# air-sensors.net
KiCad netlist of a schematic drawn in EAGLE
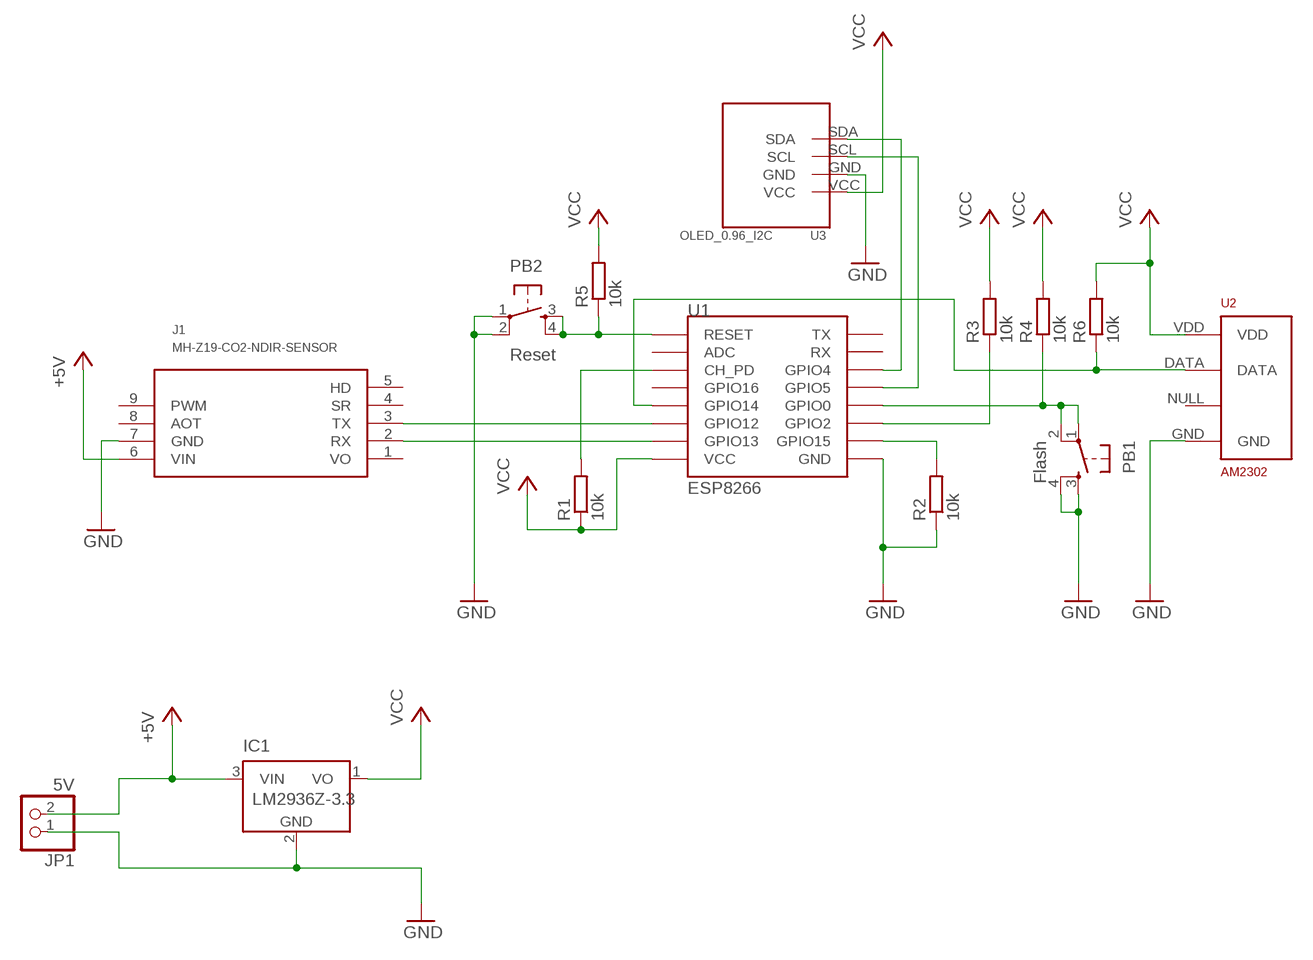
[diagram p0: schematic, sheet 1]

(export (version "E")
  (design (tool "Eeschema 10.0.6"))
  (components
    (comp (ref "IC1")
      (value "LM2936Z-3.3")
      (footprint "eagle-import:TO92")
      (fields (field (name "MF") "NATIONAL SEMICONDUCTOR") (field (name "MPN") "LM2936Z-3.3/NOPB"))
      (libsource (lib "eagle-import") (part "LM2936?Z-3.3"))
    )
    (comp (ref "J1")
      (value "MH-Z19-CO2-NDIR-SENSOR")
      (footprint "eagle-import:MH-Z19")
      (libsource (lib "eagle-import") (part "MH-Z19-CO2-NDIR-SENSOR"))
    )
    (comp (ref "JP1")
      (value "5V")
      (footprint "eagle-import:1X02")
      (libsource (lib "eagle-import") (part "PINHD-1X2"))
    )
    (comp (ref "PB1")
      (value "Flash")
      (footprint "eagle-import:TACTILE-PTH")
      (libsource (lib "eagle-import") (part "TAC_SWITCHPTH"))
    )
    (comp (ref "PB2")
      (value "Reset")
      (footprint "eagle-import:TACTILE-PTH")
      (libsource (lib "eagle-import") (part "TAC_SWITCHPTH"))
    )
    (comp (ref "R1")
      (value "10k")
      (footprint "eagle-import:0204_7")
      (libsource (lib "eagle-import") (part "R-EU_0204/7"))
    )
    (comp (ref "R2")
      (value "10k")
      (footprint "eagle-import:0204_7")
      (libsource (lib "eagle-import") (part "R-EU_0204/7"))
    )
    (comp (ref "R3")
      (value "10k")
      (footprint "eagle-import:0204_7")
      (libsource (lib "eagle-import") (part "R-EU_0204/7"))
    )
    (comp (ref "R4")
      (value "10k")
      (footprint "eagle-import:0204_7")
      (libsource (lib "eagle-import") (part "R-EU_0204/7"))
    )
    (comp (ref "R5")
      (value "10k")
      (footprint "eagle-import:0204_7")
      (libsource (lib "eagle-import") (part "R-EU_0204/7"))
    )
    (comp (ref "R6")
      (value "10k")
      (footprint "eagle-import:0204_7")
      (libsource (lib "eagle-import") (part "R-EU_0204/7"))
    )
    (comp (ref "U1")
      (value "ESP8266")
      (footprint "eagle-import:ESP12")
      (libsource (lib "eagle-import") (part "ESP12"))
    )
    (comp (ref "U2")
      (value "AM2302")
      (footprint "eagle-import:RHT03_DHT-22")
      (libsource (lib "eagle-import") (part "RHT03_DHT-22_AM2302"))
    )
    (comp (ref "U3")
      (value "OLED_0.96_I2C")
      (footprint "eagle-import:OLED_0.96_I2C")
      (libsource (lib "eagle-import") (part "OLED_0.96_I2C"))
    )
  )
  (nets
    (net (code "1") (name "+5V") (class "Default")
      (node (ref "IC1") (pin "3") (pinfunction "VIN_3") (pintype "input"))
      (node (ref "J1") (pin "6") (pinfunction "VIN_6") (pintype "power_in"))
      (node (ref "JP1") (pin "2") (pinfunction "2_2") (pintype "passive"))
    )
    (net (code "2") (name "/VO") (class "Default")
      (node (ref "J1") (pin "1") (pinfunction "VO_1") (pintype "power_in"))
    )
    (net (code "3") (name "GND") (class "Default")
      (node (ref "IC1") (pin "2") (pinfunction "GND_2") (pintype "passive"))
      (node (ref "J1") (pin "7") (pinfunction "GND_7") (pintype "power_in"))
      (node (ref "JP1") (pin "1") (pinfunction "1_1") (pintype "passive"))
      (node (ref "PB1") (pin "3") (pinfunction "3_3") (pintype "passive"))
      (node (ref "PB1") (pin "4") (pinfunction "4_4") (pintype "passive"))
      (node (ref "PB2") (pin "1") (pinfunction "1_1") (pintype "passive"))
      (node (ref "PB2") (pin "2") (pinfunction "2_2") (pintype "passive"))
      (node (ref "R2") (pin "1") (pinfunction "1_1") (pintype "passive"))
      (node (ref "U1") (pin "GND") (pinfunction "GND_GND") (pintype "bidirectional"))
      (node (ref "U2") (pin "GND") (pinfunction "GND_GND") (pintype "power_in"))
      (node (ref "U3") (pin "GND") (pinfunction "GND_GND") (pintype "bidirectional"))
    )
    (net (code "4") (name "Net-(J1-RX)") (class "Default")
      (node (ref "J1") (pin "2") (pinfunction "RX_2") (pintype "input"))
      (node (ref "U1") (pin "GPIO13") (pinfunction "GPIO13_GPIO13") (pintype "bidirectional"))
    )
    (net (code "5") (name "Net-(J1-TX)") (class "Default")
      (node (ref "J1") (pin "3") (pinfunction "TX_3") (pintype "output"))
      (node (ref "U1") (pin "GPIO12") (pinfunction "GPIO12_GPIO12") (pintype "bidirectional"))
    )
    (net (code "6") (name "Net-(PB1-Pad1)") (class "Default")
      (node (ref "PB1") (pin "1") (pinfunction "1_1") (pintype "passive"))
      (node (ref "PB1") (pin "2") (pinfunction "2_2") (pintype "passive"))
      (node (ref "R4") (pin "1") (pinfunction "1_1") (pintype "passive"))
      (node (ref "U1") (pin "GPIO0") (pinfunction "GPIO0_GPIO0") (pintype "bidirectional"))
    )
    (net (code "7") (name "Net-(PB2-Pad3)") (class "Default")
      (node (ref "PB2") (pin "3") (pinfunction "3_3") (pintype "passive"))
      (node (ref "PB2") (pin "4") (pinfunction "4_4") (pintype "passive"))
      (node (ref "R5") (pin "1") (pinfunction "1_1") (pintype "passive"))
      (node (ref "U1") (pin "RESET") (pinfunction "RESET_RESET") (pintype "bidirectional"))
    )
    (net (code "8") (name "Net-(R1-Pad2)") (class "Default")
      (node (ref "R1") (pin "2") (pinfunction "2_2") (pintype "passive"))
      (node (ref "U1") (pin "CH_PD") (pinfunction "CH_PD_CH_PD") (pintype "bidirectional"))
    )
    (net (code "9") (name "Net-(R2-Pad2)") (class "Default")
      (node (ref "R2") (pin "2") (pinfunction "2_2") (pintype "passive"))
      (node (ref "U1") (pin "GPIO15") (pinfunction "GPIO15_GPIO15") (pintype "bidirectional"))
    )
    (net (code "10") (name "Net-(R3-Pad1)") (class "Default")
      (node (ref "R3") (pin "1") (pinfunction "1_1") (pintype "passive"))
      (node (ref "U1") (pin "GPIO2") (pinfunction "GPIO2_GPIO2") (pintype "bidirectional"))
    )
    (net (code "11") (name "Net-(R6-Pad1)") (class "Default")
      (node (ref "R6") (pin "1") (pinfunction "1_1") (pintype "passive"))
      (node (ref "U1") (pin "GPIO14") (pinfunction "GPIO14_GPIO14") (pintype "bidirectional"))
      (node (ref "U2") (pin "DATA") (pinfunction "DATA_DATA") (pintype "bidirectional"))
    )
    (net (code "12") (name "Net-(U1-PadGPIO4)") (class "Default")
      (node (ref "U1") (pin "GPIO4") (pinfunction "GPIO4_GPIO4") (pintype "bidirectional"))
      (node (ref "U3") (pin "SDA") (pinfunction "SDA_SDA") (pintype "bidirectional"))
    )
    (net (code "13") (name "Net-(U1-PadGPIO5)") (class "Default")
      (node (ref "U1") (pin "GPIO5") (pinfunction "GPIO5_GPIO5") (pintype "bidirectional"))
      (node (ref "U3") (pin "SCL") (pinfunction "SCL_SCL") (pintype "bidirectional"))
    )
    (net (code "14") (name "VCC") (class "Default")
      (node (ref "IC1") (pin "1") (pinfunction "VO_1") (pintype "passive"))
      (node (ref "R1") (pin "1") (pinfunction "1_1") (pintype "passive"))
      (node (ref "R3") (pin "2") (pinfunction "2_2") (pintype "passive"))
      (node (ref "R4") (pin "2") (pinfunction "2_2") (pintype "passive"))
      (node (ref "R5") (pin "2") (pinfunction "2_2") (pintype "passive"))
      (node (ref "R6") (pin "2") (pinfunction "2_2") (pintype "passive"))
      (node (ref "U1") (pin "VCC") (pinfunction "VCC_VCC") (pintype "bidirectional"))
      (node (ref "U2") (pin "VDD") (pinfunction "VDD_VDD") (pintype "power_in"))
      (node (ref "U3") (pin "VCC") (pinfunction "VCC_VCC") (pintype "bidirectional"))
    )
    (net (code "15") (name "unconnected-(J1-AOT-Pad8)") (class "Default")
      (node (ref "J1") (pin "8") (pinfunction "AOT_8") (pintype "no_connect"))
    )
    (net (code "16") (name "unconnected-(J1-HD-Pad5)") (class "Default")
      (node (ref "J1") (pin "5") (pinfunction "HD_5") (pintype "input"))
    )
    (net (code "17") (name "unconnected-(J1-PWM-Pad9)") (class "Default")
      (node (ref "J1") (pin "9") (pinfunction "PWM_9") (pintype "output"))
    )
    (net (code "18") (name "unconnected-(J1-SR-Pad4)") (class "Default")
      (node (ref "J1") (pin "4") (pinfunction "SR_4") (pintype "no_connect"))
    )
    (net (code "19") (name "unconnected-(U1-PadADC)") (class "Default")
      (node (ref "U1") (pin "ADC") (pinfunction "ADC_ADC") (pintype "bidirectional"))
    )
    (net (code "20") (name "unconnected-(U1-PadGPIO16)") (class "Default")
      (node (ref "U1") (pin "GPIO16") (pinfunction "GPIO16_GPIO16") (pintype "bidirectional"))
    )
    (net (code "21") (name "unconnected-(U1-PadRX)") (class "Default")
      (node (ref "U1") (pin "RX") (pinfunction "RX_RX") (pintype "bidirectional"))
    )
    (net (code "22") (name "unconnected-(U1-PadTX)") (class "Default")
      (node (ref "U1") (pin "TX") (pinfunction "TX_TX") (pintype "bidirectional"))
    )
    (net (code "23") (name "unconnected-(U2-PadNULL)") (class "Default")
      (node (ref "U2") (pin "NULL") (pinfunction "NULL_NULL") (pintype "no_connect"))
    )
  )
)
